# LPCB218_-_HEC5-8.net
KiCad netlist of a schematic drawn in Altium Designer
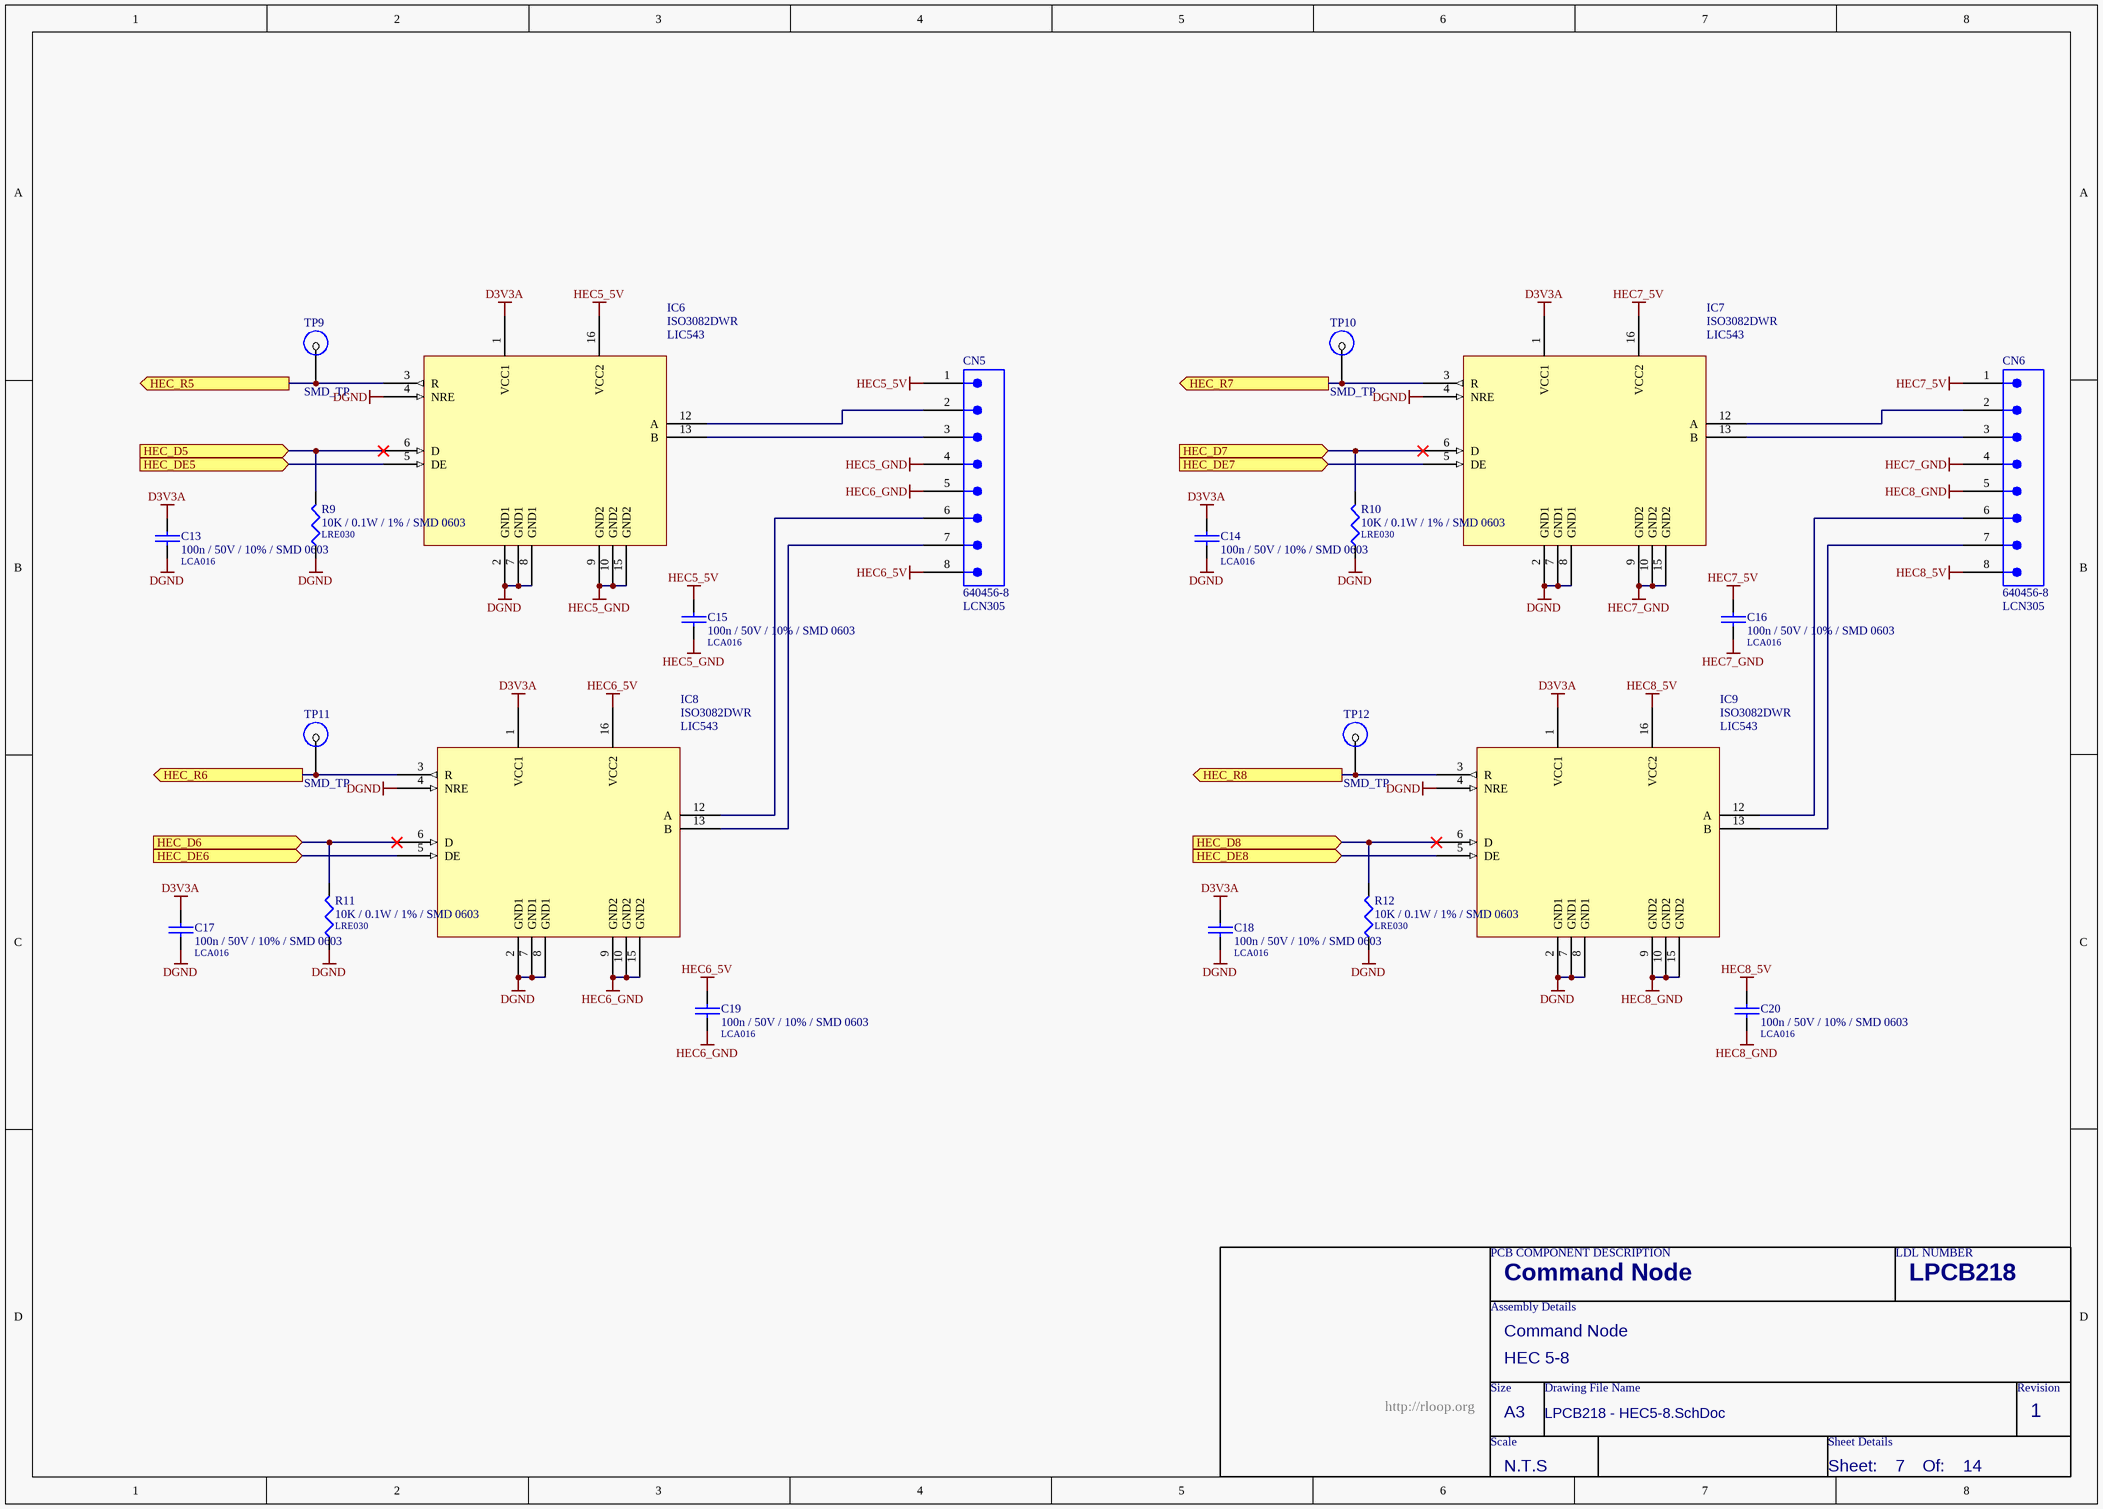
[diagram p0: LPCB218 - HEC5-8.SchDoc]

(export (version "E")
  (design (tool "Eeschema 10.0.6"))
  (components
    (comp (ref "C13")
      (value "100n / 50V / 10% / SMD 0603")
      (footprint "LFP011__CC1608-0603-IPC7351_B")
      (description "Capacitor, Ceramic Chip, 100nF (0.1uF), 50V, 5%, SMD 0603 [LCA016]")
      (fields (field (name "LDL_NUMBER") "LCA016"))
      (libsource (lib "LDL_Capacitors") (part "100n / 50V / 10% / SMD 0603"))
    )
    (comp (ref "C14")
      (value "100n / 50V / 10% / SMD 0603")
      (footprint "LFP011__CC1608-0603-IPC7351_B")
      (description "Capacitor, Ceramic Chip, 100nF (0.1uF), 50V, 5%, SMD 0603 [LCA016]")
      (fields (field (name "LDL_NUMBER") "LCA016"))
      (libsource (lib "LDL_Capacitors") (part "100n / 50V / 10% / SMD 0603"))
    )
    (comp (ref "C15")
      (value "100n / 50V / 10% / SMD 0603")
      (footprint "LFP011__CC1608-0603-IPC7351_B")
      (description "Capacitor, Ceramic Chip, 100nF (0.1uF), 50V, 5%, SMD 0603 [LCA016]")
      (fields (field (name "LDL_NUMBER") "LCA016"))
      (libsource (lib "LDL_Capacitors") (part "100n / 50V / 10% / SMD 0603"))
    )
    (comp (ref "C16")
      (value "100n / 50V / 10% / SMD 0603")
      (footprint "LFP011__CC1608-0603-IPC7351_B")
      (description "Capacitor, Ceramic Chip, 100nF (0.1uF), 50V, 5%, SMD 0603 [LCA016]")
      (fields (field (name "LDL_NUMBER") "LCA016"))
      (libsource (lib "LDL_Capacitors") (part "100n / 50V / 10% / SMD 0603"))
    )
    (comp (ref "C17")
      (value "100n / 50V / 10% / SMD 0603")
      (footprint "LFP011__CC1608-0603-IPC7351_B")
      (description "Capacitor, Ceramic Chip, 100nF (0.1uF), 50V, 5%, SMD 0603 [LCA016]")
      (fields (field (name "LDL_NUMBER") "LCA016"))
      (libsource (lib "LDL_Capacitors") (part "100n / 50V / 10% / SMD 0603"))
    )
    (comp (ref "C18")
      (value "100n / 50V / 10% / SMD 0603")
      (footprint "LFP011__CC1608-0603-IPC7351_B")
      (description "Capacitor, Ceramic Chip, 100nF (0.1uF), 50V, 5%, SMD 0603 [LCA016]")
      (fields (field (name "LDL_NUMBER") "LCA016"))
      (libsource (lib "LDL_Capacitors") (part "100n / 50V / 10% / SMD 0603"))
    )
    (comp (ref "C19")
      (value "100n / 50V / 10% / SMD 0603")
      (footprint "LFP011__CC1608-0603-IPC7351_B")
      (description "Capacitor, Ceramic Chip, 100nF (0.1uF), 50V, 5%, SMD 0603 [LCA016]")
      (fields (field (name "LDL_NUMBER") "LCA016"))
      (libsource (lib "LDL_Capacitors") (part "100n / 50V / 10% / SMD 0603"))
    )
    (comp (ref "C20")
      (value "100n / 50V / 10% / SMD 0603")
      (footprint "LFP011__CC1608-0603-IPC7351_B")
      (description "Capacitor, Ceramic Chip, 100nF (0.1uF), 50V, 5%, SMD 0603 [LCA016]")
      (fields (field (name "LDL_NUMBER") "LCA016"))
      (libsource (lib "LDL_Capacitors") (part "100n / 50V / 10% / SMD 0603"))
    )
    (comp (ref "CN5")
      (value "640456-8")
      (footprint "640456-8")
      (description "Connector, Male Header, 8 Way")
      (fields (field (name "LDL_NUMBER") "LCN305"))
      (libsource (lib "LDL_Connectors") (part "640456-8"))
    )
    (comp (ref "CN6")
      (value "640456-8")
      (footprint "640456-8")
      (description "Connector, Male Header, 8 Way")
      (fields (field (name "LDL_NUMBER") "LCN305"))
      (libsource (lib "LDL_Connectors") (part "640456-8"))
    )
    (comp (ref "IC6")
      (value "ISO3082DWR")
      (footprint "LFP068__SO-G16/G6.9")
      (description "IC, RS485 Isolator, SMD SOIC 16 [LIC543]")
      (fields (field (name "LDL_NUMBER") "LIC543"))
      (libsource (lib "LDL_Semiconductors") (part "ISO3082DWR"))
    )
    (comp (ref "IC7")
      (value "ISO3082DWR")
      (footprint "LFP068__SO-G16/G6.9")
      (description "IC, RS485 Isolator, SMD SOIC 16 [LIC543]")
      (fields (field (name "LDL_NUMBER") "LIC543"))
      (libsource (lib "LDL_Semiconductors") (part "ISO3082DWR"))
    )
    (comp (ref "IC8")
      (value "ISO3082DWR")
      (footprint "LFP068__SO-G16/G6.9")
      (description "IC, RS485 Isolator, SMD SOIC 16 [LIC543]")
      (fields (field (name "LDL_NUMBER") "LIC543"))
      (libsource (lib "LDL_Semiconductors") (part "ISO3082DWR"))
    )
    (comp (ref "IC9")
      (value "ISO3082DWR")
      (footprint "LFP068__SO-G16/G6.9")
      (description "IC, RS485 Isolator, SMD SOIC 16 [LIC543]")
      (fields (field (name "LDL_NUMBER") "LIC543"))
      (libsource (lib "LDL_Semiconductors") (part "ISO3082DWR"))
    )
    (comp (ref "R9")
      (value "10K / 0.1W / 1% / SMD 0603")
      (footprint "LFP020__CR1608-0603-IPC7351_B")
      (description "Resistor, Ceramic Chip, 10K, 0.1W, 1%, SMD 0603 [LRE030]")
      (fields (field (name "LDL_NUMBER") "LRE030"))
      (libsource (lib "LDL_Resistors") (part "10K / 0.1W / 1% / SMD 0603"))
    )
    (comp (ref "R10")
      (value "10K / 0.1W / 1% / SMD 0603")
      (footprint "LFP020__CR1608-0603-IPC7351_B")
      (description "Resistor, Ceramic Chip, 10K, 0.1W, 1%, SMD 0603 [LRE030]")
      (fields (field (name "LDL_NUMBER") "LRE030"))
      (libsource (lib "LDL_Resistors") (part "10K / 0.1W / 1% / SMD 0603"))
    )
    (comp (ref "R11")
      (value "10K / 0.1W / 1% / SMD 0603")
      (footprint "LFP020__CR1608-0603-IPC7351_B")
      (description "Resistor, Ceramic Chip, 10K, 0.1W, 1%, SMD 0603 [LRE030]")
      (fields (field (name "LDL_NUMBER") "LRE030"))
      (libsource (lib "LDL_Resistors") (part "10K / 0.1W / 1% / SMD 0603"))
    )
    (comp (ref "R12")
      (value "10K / 0.1W / 1% / SMD 0603")
      (footprint "LFP020__CR1608-0603-IPC7351_B")
      (description "Resistor, Ceramic Chip, 10K, 0.1W, 1%, SMD 0603 [LRE030]")
      (fields (field (name "LDL_NUMBER") "LRE030"))
      (libsource (lib "LDL_Resistors") (part "10K / 0.1W / 1% / SMD 0603"))
    )
    (comp (ref "TP9")
      (value "SMD_TP")
      (footprint "SMD-TP")
      (description "SMD Test Point")
      (libsource (lib "LDL_Connectors") (part "SMD_TP"))
    )
    (comp (ref "TP10")
      (value "SMD_TP")
      (footprint "SMD-TP")
      (description "SMD Test Point")
      (libsource (lib "LDL_Connectors") (part "SMD_TP"))
    )
    (comp (ref "TP11")
      (value "SMD_TP")
      (footprint "SMD-TP")
      (description "SMD Test Point")
      (libsource (lib "LDL_Connectors") (part "SMD_TP"))
    )
    (comp (ref "TP12")
      (value "SMD_TP")
      (footprint "SMD-TP")
      (description "SMD Test Point")
      (libsource (lib "LDL_Connectors") (part "SMD_TP"))
    )
  )
  (nets
    (net (code "1") (name "/HEC_D5") (class "Default")
      (node (ref "IC6") (pin "6") (pinfunction "D_6") (pintype "input"))
      (node (ref "R9") (pin "2") (pintype "passive"))
    )
    (net (code "2") (name "/HEC_D6") (class "Default")
      (node (ref "IC8") (pin "6") (pinfunction "D_6") (pintype "input"))
      (node (ref "R11") (pin "2") (pintype "passive"))
    )
    (net (code "3") (name "/HEC_D7") (class "Default")
      (node (ref "IC7") (pin "6") (pinfunction "D_6") (pintype "input"))
      (node (ref "R10") (pin "2") (pintype "passive"))
    )
    (net (code "4") (name "/HEC_D8") (class "Default")
      (node (ref "IC9") (pin "6") (pinfunction "D_6") (pintype "input"))
      (node (ref "R12") (pin "2") (pintype "passive"))
    )
    (net (code "5") (name "/HEC_DE5") (class "Default")
      (node (ref "IC6") (pin "5") (pinfunction "DE_5") (pintype "input"))
    )
    (net (code "6") (name "/HEC_DE6") (class "Default")
      (node (ref "IC8") (pin "5") (pinfunction "DE_5") (pintype "input"))
    )
    (net (code "7") (name "/HEC_DE7") (class "Default")
      (node (ref "IC7") (pin "5") (pinfunction "DE_5") (pintype "input"))
    )
    (net (code "8") (name "/HEC_DE8") (class "Default")
      (node (ref "IC9") (pin "5") (pinfunction "DE_5") (pintype "input"))
    )
    (net (code "9") (name "/HEC_R5") (class "Default")
      (node (ref "IC6") (pin "3") (pinfunction "R_3") (pintype "output"))
      (node (ref "TP9") (pin "1") (pintype "passive"))
    )
    (net (code "10") (name "/HEC_R6") (class "Default")
      (node (ref "IC8") (pin "3") (pinfunction "R_3") (pintype "output"))
      (node (ref "TP11") (pin "1") (pintype "passive"))
    )
    (net (code "11") (name "/HEC_R7") (class "Default")
      (node (ref "IC7") (pin "3") (pinfunction "R_3") (pintype "output"))
      (node (ref "TP10") (pin "1") (pintype "passive"))
    )
    (net (code "12") (name "/HEC_R8") (class "Default")
      (node (ref "IC9") (pin "3") (pinfunction "R_3") (pintype "output"))
      (node (ref "TP12") (pin "1") (pintype "passive"))
    )
    (net (code "13") (name "D3V3A") (class "Default")
      (node (ref "C13") (pin "1") (pintype "passive"))
      (node (ref "C14") (pin "1") (pintype "passive"))
      (node (ref "C17") (pin "1") (pintype "passive"))
      (node (ref "C18") (pin "1") (pintype "passive"))
      (node (ref "IC6") (pin "1") (pinfunction "VCC1_1") (pintype "power_in"))
      (node (ref "IC7") (pin "1") (pinfunction "VCC1_1") (pintype "power_in"))
      (node (ref "IC8") (pin "1") (pinfunction "VCC1_1") (pintype "power_in"))
      (node (ref "IC9") (pin "1") (pinfunction "VCC1_1") (pintype "power_in"))
    )
    (net (code "14") (name "DGND") (class "Default")
      (node (ref "C13") (pin "2") (pintype "passive"))
      (node (ref "C14") (pin "2") (pintype "passive"))
      (node (ref "C17") (pin "2") (pintype "passive"))
      (node (ref "C18") (pin "2") (pintype "passive"))
      (node (ref "IC6") (pin "2") (pinfunction "GND1_2") (pintype "power_in"))
      (node (ref "IC6") (pin "4") (pinfunction "NRE_4") (pintype "input"))
      (node (ref "IC6") (pin "7") (pinfunction "GND1_7") (pintype "power_in"))
      (node (ref "IC6") (pin "8") (pinfunction "GND1_8") (pintype "power_in"))
      (node (ref "IC7") (pin "2") (pinfunction "GND1_2") (pintype "power_in"))
      (node (ref "IC7") (pin "4") (pinfunction "NRE_4") (pintype "input"))
      (node (ref "IC7") (pin "7") (pinfunction "GND1_7") (pintype "power_in"))
      (node (ref "IC7") (pin "8") (pinfunction "GND1_8") (pintype "power_in"))
      (node (ref "IC8") (pin "2") (pinfunction "GND1_2") (pintype "power_in"))
      (node (ref "IC8") (pin "4") (pinfunction "NRE_4") (pintype "input"))
      (node (ref "IC8") (pin "7") (pinfunction "GND1_7") (pintype "power_in"))
      (node (ref "IC8") (pin "8") (pinfunction "GND1_8") (pintype "power_in"))
      (node (ref "IC9") (pin "2") (pinfunction "GND1_2") (pintype "power_in"))
      (node (ref "IC9") (pin "4") (pinfunction "NRE_4") (pintype "input"))
      (node (ref "IC9") (pin "7") (pinfunction "GND1_7") (pintype "power_in"))
      (node (ref "IC9") (pin "8") (pinfunction "GND1_8") (pintype "power_in"))
      (node (ref "R10") (pin "1") (pintype "passive"))
      (node (ref "R11") (pin "1") (pintype "passive"))
      (node (ref "R12") (pin "1") (pintype "passive"))
      (node (ref "R9") (pin "1") (pintype "passive"))
    )
    (net (code "15") (name "HEC5_5V") (class "Default")
      (node (ref "C15") (pin "1") (pintype "passive"))
      (node (ref "CN5") (pin "1") (pinfunction "1_1") (pintype "passive"))
      (node (ref "IC6") (pin "16") (pinfunction "VCC2_16") (pintype "power_in"))
    )
    (net (code "16") (name "HEC5_GND") (class "Default")
      (node (ref "C15") (pin "2") (pintype "passive"))
      (node (ref "CN5") (pin "4") (pinfunction "4_4") (pintype "passive"))
      (node (ref "IC6") (pin "10") (pinfunction "GND2_10") (pintype "power_in"))
      (node (ref "IC6") (pin "15") (pinfunction "GND2_15") (pintype "power_in"))
      (node (ref "IC6") (pin "9") (pinfunction "GND2_9") (pintype "power_in"))
    )
    (net (code "17") (name "HEC6_5V") (class "Default")
      (node (ref "C19") (pin "1") (pintype "passive"))
      (node (ref "CN5") (pin "8") (pinfunction "8_8") (pintype "passive"))
      (node (ref "IC8") (pin "16") (pinfunction "VCC2_16") (pintype "power_in"))
    )
    (net (code "18") (name "HEC6_GND") (class "Default")
      (node (ref "C19") (pin "2") (pintype "passive"))
      (node (ref "CN5") (pin "5") (pinfunction "5_5") (pintype "passive"))
      (node (ref "IC8") (pin "10") (pinfunction "GND2_10") (pintype "power_in"))
      (node (ref "IC8") (pin "15") (pinfunction "GND2_15") (pintype "power_in"))
      (node (ref "IC8") (pin "9") (pinfunction "GND2_9") (pintype "power_in"))
    )
    (net (code "19") (name "HEC7_5V") (class "Default")
      (node (ref "C16") (pin "1") (pintype "passive"))
      (node (ref "CN6") (pin "1") (pinfunction "1_1") (pintype "passive"))
      (node (ref "IC7") (pin "16") (pinfunction "VCC2_16") (pintype "power_in"))
    )
    (net (code "20") (name "HEC7_GND") (class "Default")
      (node (ref "C16") (pin "2") (pintype "passive"))
      (node (ref "CN6") (pin "4") (pinfunction "4_4") (pintype "passive"))
      (node (ref "IC7") (pin "10") (pinfunction "GND2_10") (pintype "power_in"))
      (node (ref "IC7") (pin "15") (pinfunction "GND2_15") (pintype "power_in"))
      (node (ref "IC7") (pin "9") (pinfunction "GND2_9") (pintype "power_in"))
    )
    (net (code "21") (name "HEC8_5V") (class "Default")
      (node (ref "C20") (pin "1") (pintype "passive"))
      (node (ref "CN6") (pin "8") (pinfunction "8_8") (pintype "passive"))
      (node (ref "IC9") (pin "16") (pinfunction "VCC2_16") (pintype "power_in"))
    )
    (net (code "22") (name "HEC8_GND") (class "Default")
      (node (ref "C20") (pin "2") (pintype "passive"))
      (node (ref "CN6") (pin "5") (pinfunction "5_5") (pintype "passive"))
      (node (ref "IC9") (pin "10") (pinfunction "GND2_10") (pintype "power_in"))
      (node (ref "IC9") (pin "15") (pinfunction "GND2_15") (pintype "power_in"))
      (node (ref "IC9") (pin "9") (pinfunction "GND2_9") (pintype "power_in"))
    )
    (net (code "23") (name "Net-(IC6-A)") (class "Default")
      (node (ref "CN5") (pin "2") (pinfunction "2_2") (pintype "passive"))
      (node (ref "IC6") (pin "12") (pinfunction "A_12") (pintype "passive"))
    )
    (net (code "24") (name "Net-(IC6-B)") (class "Default")
      (node (ref "CN5") (pin "3") (pinfunction "3_3") (pintype "passive"))
      (node (ref "IC6") (pin "13") (pinfunction "B_13") (pintype "passive"))
    )
    (net (code "25") (name "Net-(IC7-A)") (class "Default")
      (node (ref "CN6") (pin "2") (pinfunction "2_2") (pintype "passive"))
      (node (ref "IC7") (pin "12") (pinfunction "A_12") (pintype "passive"))
    )
    (net (code "26") (name "Net-(IC7-B)") (class "Default")
      (node (ref "CN6") (pin "3") (pinfunction "3_3") (pintype "passive"))
      (node (ref "IC7") (pin "13") (pinfunction "B_13") (pintype "passive"))
    )
    (net (code "27") (name "Net-(IC8-A)") (class "Default")
      (node (ref "CN5") (pin "6") (pinfunction "6_6") (pintype "passive"))
      (node (ref "IC8") (pin "12") (pinfunction "A_12") (pintype "passive"))
    )
    (net (code "28") (name "Net-(IC8-B)") (class "Default")
      (node (ref "CN5") (pin "7") (pinfunction "7_7") (pintype "passive"))
      (node (ref "IC8") (pin "13") (pinfunction "B_13") (pintype "passive"))
    )
    (net (code "29") (name "Net-(IC9-A)") (class "Default")
      (node (ref "CN6") (pin "6") (pinfunction "6_6") (pintype "passive"))
      (node (ref "IC9") (pin "12") (pinfunction "A_12") (pintype "passive"))
    )
    (net (code "30") (name "Net-(IC9-B)") (class "Default")
      (node (ref "CN6") (pin "7") (pinfunction "7_7") (pintype "passive"))
      (node (ref "IC9") (pin "13") (pinfunction "B_13") (pintype "passive"))
    )
  )
)
